# Register.net
KiCad netlist of a schematic drawn in EAGLE
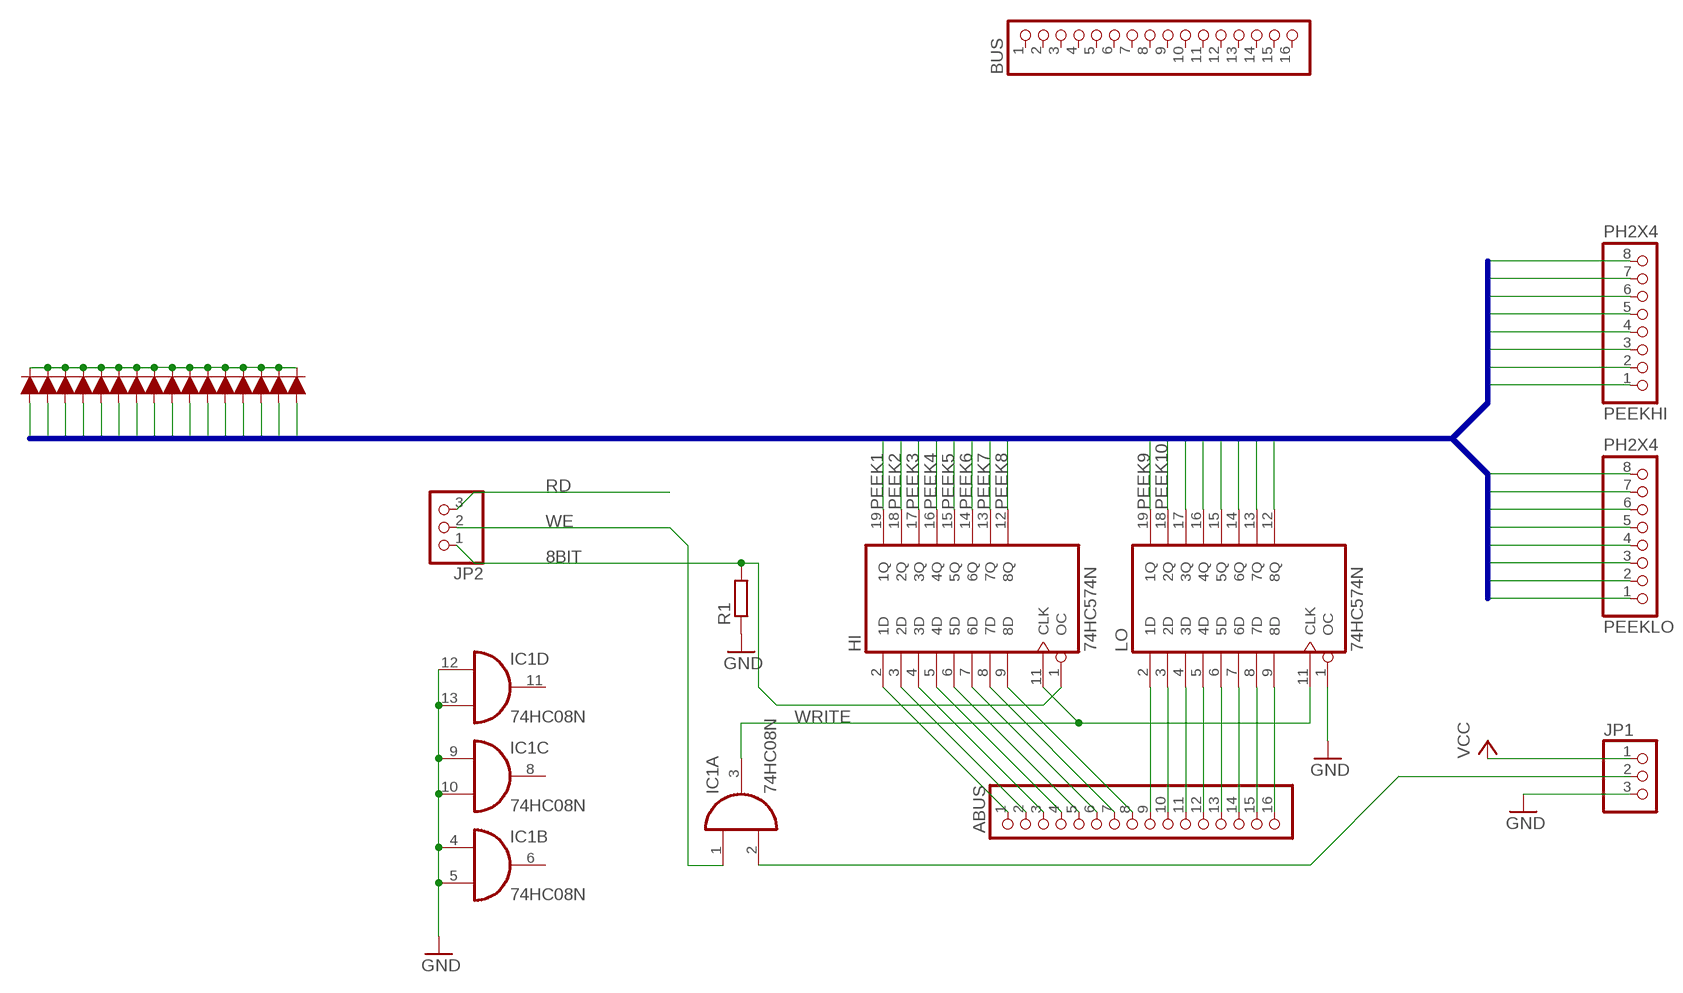
[diagram p0: schematic, sheet 1]

(export (version "E")
  (design (tool "Eeschema 10.0.6"))
  (components
    (comp (ref "ABUS")
      (value "PINHD-1X16")
      (footprint "eagle-import:1X16")
      (libsource (lib "eagle-import") (part "PINHD-1X16"))
    )
    (comp (ref "BUS")
      (value "PINHD-1X16")
      (footprint "eagle-import:1X16")
      (libsource (lib "eagle-import") (part "PINHD-1X16"))
    )
    (comp (ref "D1")
      (value "200mA/100V/1V")
      (footprint "eagle-import:DIODE-1N4148")
      (libsource (lib "eagle-import") (part "DIODE-1N4148"))
    )
    (comp (ref "D2")
      (value "200mA/100V/1V")
      (footprint "eagle-import:DIODE-1N4148")
      (libsource (lib "eagle-import") (part "DIODE-1N4148"))
    )
    (comp (ref "D3")
      (value "200mA/100V/1V")
      (footprint "eagle-import:DIODE-1N4148")
      (libsource (lib "eagle-import") (part "DIODE-1N4148"))
    )
    (comp (ref "D4")
      (value "200mA/100V/1V")
      (footprint "eagle-import:DIODE-1N4148")
      (libsource (lib "eagle-import") (part "DIODE-1N4148"))
    )
    (comp (ref "D5")
      (value "200mA/100V/1V")
      (footprint "eagle-import:DIODE-1N4148")
      (libsource (lib "eagle-import") (part "DIODE-1N4148"))
    )
    (comp (ref "D6")
      (value "200mA/100V/1V")
      (footprint "eagle-import:DIODE-1N4148")
      (libsource (lib "eagle-import") (part "DIODE-1N4148"))
    )
    (comp (ref "D7")
      (value "200mA/100V/1V")
      (footprint "eagle-import:DIODE-1N4148")
      (libsource (lib "eagle-import") (part "DIODE-1N4148"))
    )
    (comp (ref "D8")
      (value "200mA/100V/1V")
      (footprint "eagle-import:DIODE-1N4148")
      (libsource (lib "eagle-import") (part "DIODE-1N4148"))
    )
    (comp (ref "D9")
      (value "200mA/100V/1V")
      (footprint "eagle-import:DIODE-1N4148")
      (libsource (lib "eagle-import") (part "DIODE-1N4148"))
    )
    (comp (ref "D10")
      (value "200mA/100V/1V")
      (footprint "eagle-import:DIODE-1N4148")
      (libsource (lib "eagle-import") (part "DIODE-1N4148"))
    )
    (comp (ref "D11")
      (value "200mA/100V/1V")
      (footprint "eagle-import:DIODE-1N4148")
      (libsource (lib "eagle-import") (part "DIODE-1N4148"))
    )
    (comp (ref "D12")
      (value "200mA/100V/1V")
      (footprint "eagle-import:DIODE-1N4148")
      (libsource (lib "eagle-import") (part "DIODE-1N4148"))
    )
    (comp (ref "D13")
      (value "200mA/100V/1V")
      (footprint "eagle-import:DIODE-1N4148")
      (libsource (lib "eagle-import") (part "DIODE-1N4148"))
    )
    (comp (ref "D14")
      (value "200mA/100V/1V")
      (footprint "eagle-import:DIODE-1N4148")
      (libsource (lib "eagle-import") (part "DIODE-1N4148"))
    )
    (comp (ref "D15")
      (value "200mA/100V/1V")
      (footprint "eagle-import:DIODE-1N4148")
      (libsource (lib "eagle-import") (part "DIODE-1N4148"))
    )
    (comp (ref "D16")
      (value "200mA/100V/1V")
      (footprint "eagle-import:DIODE-1N4148")
      (libsource (lib "eagle-import") (part "DIODE-1N4148"))
    )
    (comp (ref "HI")
      (value "74HC574N")
      (footprint "eagle-import:DIL20")
      (libsource (lib "eagle-import") (part "74574NHC"))
    )
    (comp (ref "IC1")
      (value "74HC08N")
      (footprint "eagle-import:DIL14")
      (libsource (lib "eagle-import") (part "7408NHC"))
    )
    (comp (ref "JP1")
      (value "PINHD-1X3")
      (footprint "eagle-import:1X03")
      (libsource (lib "eagle-import") (part "PINHD-1X3"))
    )
    (comp (ref "JP2")
      (value "PINHD-1X3")
      (footprint "eagle-import:1X03")
      (libsource (lib "eagle-import") (part "pinhead_325_PINHD-1X3"))
    )
    (comp (ref "LO")
      (value "74HC574N")
      (footprint "eagle-import:DIL20")
      (libsource (lib "eagle-import") (part "74574NHC"))
    )
    (comp (ref "PEEKHI")
      (value "PH2X4")
      (footprint "eagle-import:2X04")
      (libsource (lib "eagle-import") (part "PH2X4"))
    )
    (comp (ref "PEEKLO")
      (value "PH2X4")
      (footprint "eagle-import:2X04")
      (libsource (lib "eagle-import") (part "PH2X4"))
    )
    (comp (ref "R1")
      (value "R-EU_0204/7")
      (footprint "eagle-import:0204_7")
      (libsource (lib "eagle-import") (part "R-EU_0204/7"))
    )
  )
  (nets
    (net (code "1") (name "/8BIT") (class "Default")
      (node (ref "HI") (pin "1") (pinfunction "OC_1") (pintype "input"))
      (node (ref "JP2") (pin "1") (pinfunction "1_1") (pintype "passive"))
      (node (ref "R1") (pin "2") (pinfunction "2_2") (pintype "passive"))
    )
    (net (code "2") (name "/PEEK1") (class "Default")
      (node (ref "D16") (pin "A") (pinfunction "A_A") (pintype "passive"))
      (node (ref "HI") (pin "19") (pinfunction "1Q_19") (pintype "tri_state"))
      (node (ref "PEEKHI") (pin "1") (pinfunction "1_1") (pintype "passive"))
    )
    (net (code "3") (name "/PEEK2") (class "Default")
      (node (ref "D15") (pin "A") (pinfunction "A_A") (pintype "passive"))
      (node (ref "HI") (pin "18") (pinfunction "2Q_18") (pintype "tri_state"))
      (node (ref "PEEKHI") (pin "2") (pinfunction "2_2") (pintype "passive"))
    )
    (net (code "4") (name "/PEEK3") (class "Default")
      (node (ref "D14") (pin "A") (pinfunction "A_A") (pintype "passive"))
      (node (ref "HI") (pin "17") (pinfunction "3Q_17") (pintype "tri_state"))
      (node (ref "PEEKHI") (pin "3") (pinfunction "3_3") (pintype "passive"))
    )
    (net (code "5") (name "/PEEK4") (class "Default")
      (node (ref "D1") (pin "A") (pinfunction "A_A") (pintype "passive"))
      (node (ref "HI") (pin "16") (pinfunction "4Q_16") (pintype "tri_state"))
      (node (ref "PEEKHI") (pin "4") (pinfunction "4_4") (pintype "passive"))
    )
    (net (code "6") (name "/PEEK5") (class "Default")
      (node (ref "D13") (pin "A") (pinfunction "A_A") (pintype "passive"))
      (node (ref "HI") (pin "15") (pinfunction "5Q_15") (pintype "tri_state"))
      (node (ref "PEEKHI") (pin "5") (pinfunction "5_5") (pintype "passive"))
    )
    (net (code "7") (name "/PEEK6") (class "Default")
      (node (ref "D2") (pin "A") (pinfunction "A_A") (pintype "passive"))
      (node (ref "HI") (pin "14") (pinfunction "6Q_14") (pintype "tri_state"))
      (node (ref "PEEKHI") (pin "6") (pinfunction "6_6") (pintype "passive"))
    )
    (net (code "8") (name "/PEEK7") (class "Default")
      (node (ref "D12") (pin "A") (pinfunction "A_A") (pintype "passive"))
      (node (ref "HI") (pin "13") (pinfunction "7Q_13") (pintype "tri_state"))
      (node (ref "PEEKHI") (pin "7") (pinfunction "7_7") (pintype "passive"))
    )
    (net (code "9") (name "/PEEK8") (class "Default")
      (node (ref "D3") (pin "A") (pinfunction "A_A") (pintype "passive"))
      (node (ref "HI") (pin "12") (pinfunction "8Q_12") (pintype "tri_state"))
      (node (ref "PEEKHI") (pin "8") (pinfunction "8_8") (pintype "passive"))
    )
    (net (code "10") (name "/PEEK9") (class "Default")
      (node (ref "D11") (pin "A") (pinfunction "A_A") (pintype "passive"))
      (node (ref "LO") (pin "19") (pinfunction "1Q_19") (pintype "tri_state"))
      (node (ref "PEEKLO") (pin "1") (pinfunction "1_1") (pintype "passive"))
    )
    (net (code "11") (name "/PEEK10") (class "Default")
      (node (ref "D4") (pin "A") (pinfunction "A_A") (pintype "passive"))
      (node (ref "LO") (pin "18") (pinfunction "2Q_18") (pintype "tri_state"))
      (node (ref "PEEKLO") (pin "2") (pinfunction "2_2") (pintype "passive"))
    )
    (net (code "12") (name "/PEEK11") (class "Default")
      (node (ref "D10") (pin "A") (pinfunction "A_A") (pintype "passive"))
      (node (ref "LO") (pin "17") (pinfunction "3Q_17") (pintype "tri_state"))
      (node (ref "PEEKLO") (pin "3") (pinfunction "3_3") (pintype "passive"))
    )
    (net (code "13") (name "/PEEK12") (class "Default")
      (node (ref "D5") (pin "A") (pinfunction "A_A") (pintype "passive"))
      (node (ref "LO") (pin "16") (pinfunction "4Q_16") (pintype "tri_state"))
      (node (ref "PEEKLO") (pin "4") (pinfunction "4_4") (pintype "passive"))
    )
    (net (code "14") (name "/PEEK13") (class "Default")
      (node (ref "D9") (pin "A") (pinfunction "A_A") (pintype "passive"))
      (node (ref "LO") (pin "14") (pinfunction "6Q_14") (pintype "tri_state"))
      (node (ref "LO") (pin "15") (pinfunction "5Q_15") (pintype "tri_state"))
      (node (ref "PEEKLO") (pin "5") (pinfunction "5_5") (pintype "passive"))
    )
    (net (code "15") (name "/PEEK14") (class "Default")
      (node (ref "D6") (pin "A") (pinfunction "A_A") (pintype "passive"))
      (node (ref "PEEKLO") (pin "6") (pinfunction "6_6") (pintype "passive"))
    )
    (net (code "16") (name "/PEEK15") (class "Default")
      (node (ref "D7") (pin "A") (pinfunction "A_A") (pintype "passive"))
      (node (ref "LO") (pin "13") (pinfunction "7Q_13") (pintype "tri_state"))
      (node (ref "PEEKLO") (pin "7") (pinfunction "7_7") (pintype "passive"))
    )
    (net (code "17") (name "/PEEK16") (class "Default")
      (node (ref "D8") (pin "A") (pinfunction "A_A") (pintype "passive"))
      (node (ref "LO") (pin "12") (pinfunction "8Q_12") (pintype "tri_state"))
      (node (ref "PEEKLO") (pin "8") (pinfunction "8_8") (pintype "passive"))
    )
    (net (code "18") (name "/RD") (class "Default")
      (node (ref "JP2") (pin "3") (pinfunction "3_3") (pintype "passive"))
    )
    (net (code "19") (name "/WE") (class "Default")
      (node (ref "IC1") (pin "1") (pinfunction "I0_1") (pintype "input"))
      (node (ref "JP2") (pin "2") (pinfunction "2_2") (pintype "passive"))
    )
    (net (code "20") (name "/WRITE") (class "Default")
      (node (ref "HI") (pin "11") (pinfunction "CLK_11") (pintype "input"))
      (node (ref "IC1") (pin "3") (pinfunction "O_3") (pintype "output"))
      (node (ref "LO") (pin "11") (pinfunction "CLK_11") (pintype "input"))
    )
    (net (code "21") (name "GND") (class "Default")
      (node (ref "IC1") (pin "10") (pinfunction "I1_10") (pintype "input"))
      (node (ref "IC1") (pin "12") (pinfunction "I0_12") (pintype "input"))
      (node (ref "IC1") (pin "13") (pinfunction "I1_13") (pintype "input"))
      (node (ref "IC1") (pin "4") (pinfunction "I0_4") (pintype "input"))
      (node (ref "IC1") (pin "5") (pinfunction "I1_5") (pintype "input"))
      (node (ref "IC1") (pin "9") (pinfunction "I0_9") (pintype "input"))
      (node (ref "JP1") (pin "3") (pinfunction "3_3") (pintype "passive"))
      (node (ref "LO") (pin "1") (pinfunction "OC_1") (pintype "input"))
      (node (ref "R1") (pin "1") (pinfunction "1_1") (pintype "passive"))
    )
    (net (code "22") (name "Net-(D1-PadC)") (class "Default")
      (node (ref "D1") (pin "C") (pinfunction "C_C") (pintype "passive"))
      (node (ref "D10") (pin "C") (pinfunction "C_C") (pintype "passive"))
      (node (ref "D11") (pin "C") (pinfunction "C_C") (pintype "passive"))
      (node (ref "D12") (pin "C") (pinfunction "C_C") (pintype "passive"))
      (node (ref "D13") (pin "C") (pinfunction "C_C") (pintype "passive"))
      (node (ref "D14") (pin "C") (pinfunction "C_C") (pintype "passive"))
      (node (ref "D15") (pin "C") (pinfunction "C_C") (pintype "passive"))
      (node (ref "D16") (pin "C") (pinfunction "C_C") (pintype "passive"))
      (node (ref "D2") (pin "C") (pinfunction "C_C") (pintype "passive"))
      (node (ref "D3") (pin "C") (pinfunction "C_C") (pintype "passive"))
      (node (ref "D4") (pin "C") (pinfunction "C_C") (pintype "passive"))
      (node (ref "D5") (pin "C") (pinfunction "C_C") (pintype "passive"))
      (node (ref "D6") (pin "C") (pinfunction "C_C") (pintype "passive"))
      (node (ref "D7") (pin "C") (pinfunction "C_C") (pintype "passive"))
      (node (ref "D8") (pin "C") (pinfunction "C_C") (pintype "passive"))
      (node (ref "D9") (pin "C") (pinfunction "C_C") (pintype "passive"))
    )
    (net (code "23") (name "Net-(HIA-1D)") (class "Default")
      (node (ref "ABUS") (pin "1") (pinfunction "1_1") (pintype "passive"))
      (node (ref "HI") (pin "2") (pinfunction "1D_2") (pintype "input"))
    )
    (net (code "24") (name "Net-(HIA-2D)") (class "Default")
      (node (ref "ABUS") (pin "2") (pinfunction "2_2") (pintype "passive"))
      (node (ref "HI") (pin "3") (pinfunction "2D_3") (pintype "input"))
    )
    (net (code "25") (name "Net-(HIA-3D)") (class "Default")
      (node (ref "ABUS") (pin "3") (pinfunction "3_3") (pintype "passive"))
      (node (ref "HI") (pin "4") (pinfunction "3D_4") (pintype "input"))
    )
    (net (code "26") (name "Net-(HIA-4D)") (class "Default")
      (node (ref "ABUS") (pin "4") (pinfunction "4_4") (pintype "passive"))
      (node (ref "HI") (pin "5") (pinfunction "4D_5") (pintype "input"))
    )
    (net (code "27") (name "Net-(HIA-5D)") (class "Default")
      (node (ref "ABUS") (pin "5") (pinfunction "5_5") (pintype "passive"))
      (node (ref "HI") (pin "6") (pinfunction "5D_6") (pintype "input"))
    )
    (net (code "28") (name "Net-(HIA-6D)") (class "Default")
      (node (ref "ABUS") (pin "6") (pinfunction "6_6") (pintype "passive"))
      (node (ref "HI") (pin "7") (pinfunction "6D_7") (pintype "input"))
    )
    (net (code "29") (name "Net-(HIA-7D)") (class "Default")
      (node (ref "ABUS") (pin "7") (pinfunction "7_7") (pintype "passive"))
      (node (ref "HI") (pin "8") (pinfunction "7D_8") (pintype "input"))
    )
    (net (code "30") (name "Net-(HIA-8D)") (class "Default")
      (node (ref "ABUS") (pin "8") (pinfunction "8_8") (pintype "passive"))
      (node (ref "HI") (pin "9") (pinfunction "8D_9") (pintype "input"))
    )
    (net (code "31") (name "Net-(IC1A-I1)") (class "Default")
      (node (ref "IC1") (pin "2") (pinfunction "I1_2") (pintype "input"))
      (node (ref "JP1") (pin "2") (pinfunction "2_2") (pintype "passive"))
    )
    (net (code "32") (name "Net-(LOA-1D)") (class "Default")
      (node (ref "ABUS") (pin "9") (pinfunction "9_9") (pintype "passive"))
      (node (ref "LO") (pin "2") (pinfunction "1D_2") (pintype "input"))
    )
    (net (code "33") (name "Net-(LOA-2D)") (class "Default")
      (node (ref "ABUS") (pin "10") (pinfunction "10_10") (pintype "passive"))
      (node (ref "LO") (pin "3") (pinfunction "2D_3") (pintype "input"))
    )
    (net (code "34") (name "Net-(LOA-3D)") (class "Default")
      (node (ref "ABUS") (pin "11") (pinfunction "11_11") (pintype "passive"))
      (node (ref "LO") (pin "4") (pinfunction "3D_4") (pintype "input"))
    )
    (net (code "35") (name "Net-(LOA-4D)") (class "Default")
      (node (ref "ABUS") (pin "12") (pinfunction "12_12") (pintype "passive"))
      (node (ref "LO") (pin "5") (pinfunction "4D_5") (pintype "input"))
    )
    (net (code "36") (name "Net-(LOA-5D)") (class "Default")
      (node (ref "ABUS") (pin "13") (pinfunction "13_13") (pintype "passive"))
      (node (ref "LO") (pin "6") (pinfunction "5D_6") (pintype "input"))
    )
    (net (code "37") (name "Net-(LOA-6D)") (class "Default")
      (node (ref "ABUS") (pin "14") (pinfunction "14_14") (pintype "passive"))
      (node (ref "LO") (pin "7") (pinfunction "6D_7") (pintype "input"))
    )
    (net (code "38") (name "Net-(LOA-7D)") (class "Default")
      (node (ref "ABUS") (pin "15") (pinfunction "15_15") (pintype "passive"))
      (node (ref "LO") (pin "8") (pinfunction "7D_8") (pintype "input"))
    )
    (net (code "39") (name "Net-(LOA-8D)") (class "Default")
      (node (ref "ABUS") (pin "16") (pinfunction "16_16") (pintype "passive"))
      (node (ref "LO") (pin "9") (pinfunction "8D_9") (pintype "input"))
    )
    (net (code "40") (name "VCC") (class "Default")
      (node (ref "JP1") (pin "1") (pinfunction "1_1") (pintype "passive"))
    )
    (net (code "41") (name "unconnected-(BUS-Pad1)") (class "Default")
      (node (ref "BUS") (pin "1") (pinfunction "1_1") (pintype "passive"))
    )
    (net (code "42") (name "unconnected-(BUS-Pad2)") (class "Default")
      (node (ref "BUS") (pin "2") (pinfunction "2_2") (pintype "passive"))
    )
    (net (code "43") (name "unconnected-(BUS-Pad3)") (class "Default")
      (node (ref "BUS") (pin "3") (pinfunction "3_3") (pintype "passive"))
    )
    (net (code "44") (name "unconnected-(BUS-Pad4)") (class "Default")
      (node (ref "BUS") (pin "4") (pinfunction "4_4") (pintype "passive"))
    )
    (net (code "45") (name "unconnected-(BUS-Pad5)") (class "Default")
      (node (ref "BUS") (pin "5") (pinfunction "5_5") (pintype "passive"))
    )
    (net (code "46") (name "unconnected-(BUS-Pad6)") (class "Default")
      (node (ref "BUS") (pin "6") (pinfunction "6_6") (pintype "passive"))
    )
    (net (code "47") (name "unconnected-(BUS-Pad7)") (class "Default")
      (node (ref "BUS") (pin "7") (pinfunction "7_7") (pintype "passive"))
    )
    (net (code "48") (name "unconnected-(BUS-Pad8)") (class "Default")
      (node (ref "BUS") (pin "8") (pinfunction "8_8") (pintype "passive"))
    )
    (net (code "49") (name "unconnected-(BUS-Pad9)") (class "Default")
      (node (ref "BUS") (pin "9") (pinfunction "9_9") (pintype "passive"))
    )
    (net (code "50") (name "unconnected-(BUS-Pad10)") (class "Default")
      (node (ref "BUS") (pin "10") (pinfunction "10_10") (pintype "passive"))
    )
    (net (code "51") (name "unconnected-(BUS-Pad11)") (class "Default")
      (node (ref "BUS") (pin "11") (pinfunction "11_11") (pintype "passive"))
    )
    (net (code "52") (name "unconnected-(BUS-Pad12)") (class "Default")
      (node (ref "BUS") (pin "12") (pinfunction "12_12") (pintype "passive"))
    )
    (net (code "53") (name "unconnected-(BUS-Pad13)") (class "Default")
      (node (ref "BUS") (pin "13") (pinfunction "13_13") (pintype "passive"))
    )
    (net (code "54") (name "unconnected-(BUS-Pad14)") (class "Default")
      (node (ref "BUS") (pin "14") (pinfunction "14_14") (pintype "passive"))
    )
    (net (code "55") (name "unconnected-(BUS-Pad15)") (class "Default")
      (node (ref "BUS") (pin "15") (pinfunction "15_15") (pintype "passive"))
    )
    (net (code "56") (name "unconnected-(BUS-Pad16)") (class "Default")
      (node (ref "BUS") (pin "16") (pinfunction "16_16") (pintype "passive"))
    )
    (net (code "57") (name "unconnected-(IC1B-O-Pad6)") (class "Default")
      (node (ref "IC1") (pin "6") (pinfunction "O_6") (pintype "output"))
    )
    (net (code "58") (name "unconnected-(IC1C-O-Pad8)") (class "Default")
      (node (ref "IC1") (pin "8") (pinfunction "O_8") (pintype "output"))
    )
    (net (code "59") (name "unconnected-(IC1D-O-Pad11)") (class "Default")
      (node (ref "IC1") (pin "11") (pinfunction "O_11") (pintype "output"))
    )
  )
)
